# LED_aluminum.net
KiCad netlist of a schematic drawn in Altium Designer
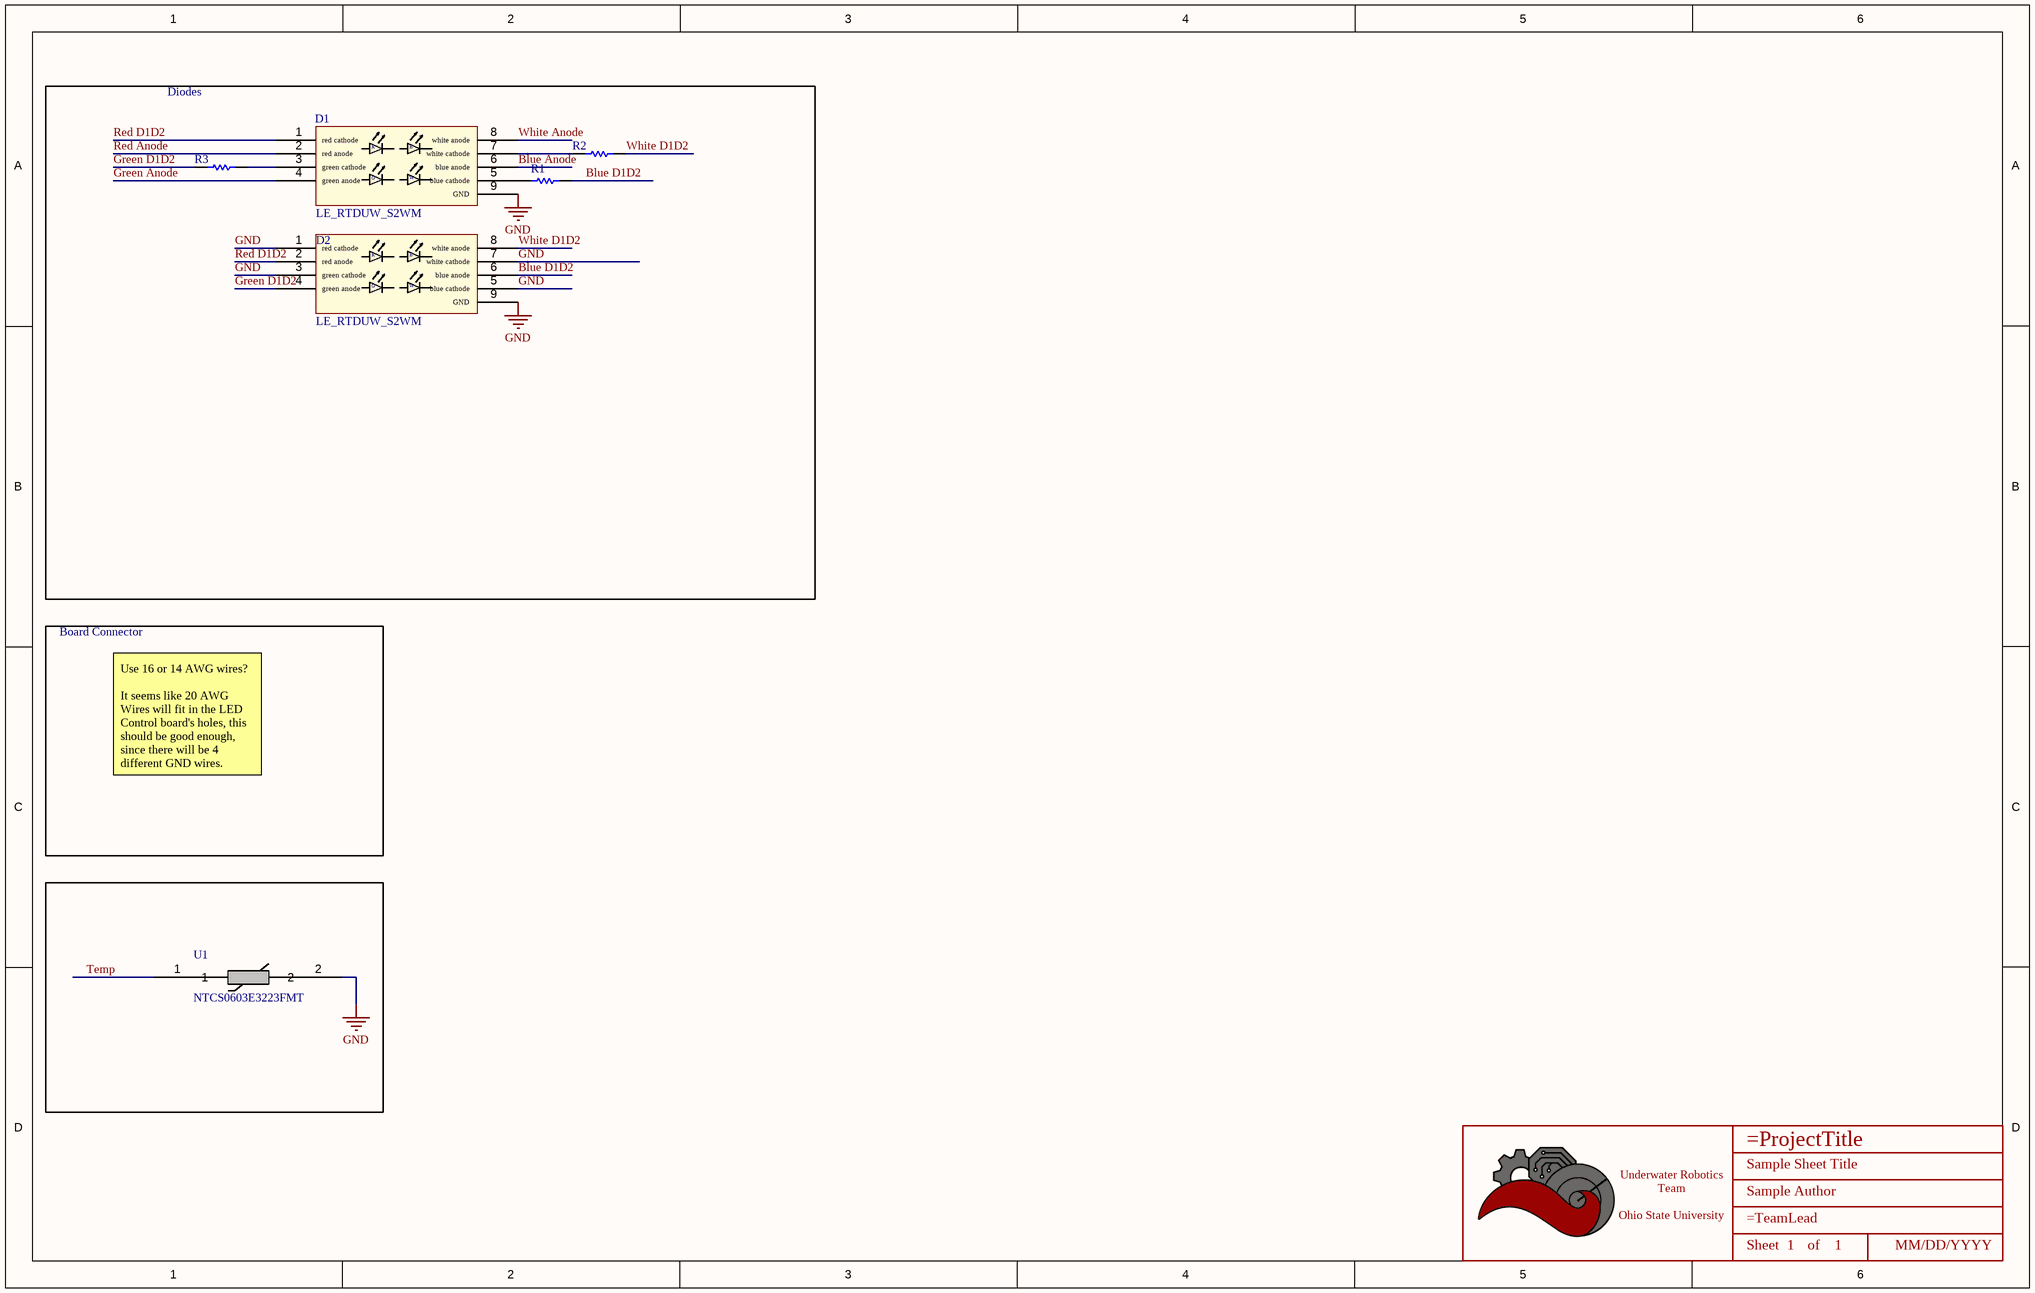
[diagram p0: LED_aluminum.SchDoc]

(export (version "E")
  (design (tool "Eeschema 10.0.6"))
  (components
    (comp (ref "*")
      (value "Title_Block")
      (footprint "LOGO")
      (description "UWRT Schematic Title Block Template\r\n\r\nCreated June 2021, Dylan Trainor")
      (libsource (lib "UWRT") (part "Title_Block"))
    )
    (comp (ref "D1")
      (value "LE_RTDUW_S2WM")
      (footprint "LE_RTDUW_S2WM")
      (description "LED OSTAR RGBW 625/527/453NM SMD")
      (libsource (lib "Diodes") (part "LE_RTDUW_S2WM"))
    )
    (comp (ref "D2")
      (value "LE_RTDUW_S2WM")
      (footprint "LE_RTDUW_S2WM")
      (description "LED OSTAR RGBW 625/527/453NM SMD")
      (libsource (lib "Diodes") (part "LE_RTDUW_S2WM"))
    )
    (comp (ref "R1")
      (value "Jumper 2512(6432)")
      (footprint "RESC2512(6432)_L")
      (description "Jumper 2512 (6432 Metric)")
      (fields (field (name "TOLERANCE") "None"))
      (libsource (lib "") (part "RES_1"))
    )
    (comp (ref "R2")
      (value "ERJ-8GEY0R00V")
      (footprint "RESC3216X70X50NL05T20")
      (fields (field (name "MANUFACTURER") "Panasonic"))
      (libsource (lib "Altium Content Vault") (part "RES"))
    )
    (comp (ref "R3")
      (value "Jumper 2512(6432)")
      (footprint "RESC2512(6432)_L")
      (fields (field (name "MANUFACTURER") "Panasonic") (field (name "PART NUMBER") "ERJ-8GEY0R00V"))
      (libsource (lib "Altium Content Vault") (part "RES"))
    )
    (comp (ref "U1")
      (value "NTCS0603E3223FMT")
      (footprint "NTCS0603_VIS")
      (fields (field (name "TOLERANCE") "1%"))
      (libsource (lib "Altium Content Vault") (part "NTCS0603E3223FMT"))
    )
  )
  (nets
    (net (code "1") (name "/Blue Anode") (class "Default")
      (node (ref "D1") (pin "6") (pinfunction "blue_anode_6") (pintype "passive"))
    )
    (net (code "2") (name "/Blue D1D2") (class "Default")
      (node (ref "D2") (pin "6") (pinfunction "blue_anode_6") (pintype "passive"))
      (node (ref "R1") (pin "2") (pinfunction "2_2") (pintype "passive"))
    )
    (net (code "3") (name "/Green Anode") (class "Default")
      (node (ref "D1") (pin "4") (pinfunction "green_anode_4") (pintype "passive"))
    )
    (net (code "4") (name "/Green D1D2") (class "Default")
      (node (ref "D2") (pin "4") (pinfunction "green_anode_4") (pintype "passive"))
      (node (ref "R3") (pin "2") (pinfunction "2_2") (pintype "passive"))
    )
    (net (code "5") (name "/Red Anode") (class "Default")
      (node (ref "D1") (pin "2") (pinfunction "red_anode_2") (pintype "passive"))
    )
    (net (code "6") (name "/Red D1D2") (class "Default")
      (node (ref "D1") (pin "1") (pinfunction "red_cathode_1") (pintype "passive"))
      (node (ref "D2") (pin "2") (pinfunction "red_anode_2") (pintype "passive"))
    )
    (net (code "7") (name "/Temp") (class "Default")
      (node (ref "U1") (pin "1") (pinfunction "1_1") (pintype "passive"))
    )
    (net (code "8") (name "/White Anode") (class "Default")
      (node (ref "D1") (pin "8") (pinfunction "white_anode_8") (pintype "passive"))
    )
    (net (code "9") (name "/White D1D2") (class "Default")
      (node (ref "D2") (pin "8") (pinfunction "white_anode_8") (pintype "passive"))
      (node (ref "R2") (pin "1") (pinfunction "1_1") (pintype "passive"))
    )
    (net (code "10") (name "GND") (class "Default")
      (node (ref "D1") (pin "9") (pinfunction "GND_9") (pintype "passive"))
      (node (ref "D2") (pin "1") (pinfunction "red_cathode_1") (pintype "passive"))
      (node (ref "D2") (pin "3") (pinfunction "green_cathode_3") (pintype "passive"))
      (node (ref "D2") (pin "5") (pinfunction "blue_cathode_5") (pintype "passive"))
      (node (ref "D2") (pin "7") (pinfunction "white_cathode_7") (pintype "passive"))
      (node (ref "D2") (pin "9") (pinfunction "GND_9") (pintype "passive"))
      (node (ref "U1") (pin "2") (pinfunction "2_2") (pintype "passive"))
    )
    (net (code "11") (name "Net-(D1-blue_cathode)") (class "Default")
      (node (ref "D1") (pin "5") (pinfunction "blue_cathode_5") (pintype "passive"))
      (node (ref "R1") (pin "1") (pinfunction "1_1") (pintype "passive"))
    )
    (net (code "12") (name "Net-(D1-green_cathode)") (class "Default")
      (node (ref "D1") (pin "3") (pinfunction "green_cathode_3") (pintype "passive"))
      (node (ref "R3") (pin "1") (pinfunction "1_1") (pintype "passive"))
    )
    (net (code "13") (name "Net-(D1-white_cathode)") (class "Default")
      (node (ref "D1") (pin "7") (pinfunction "white_cathode_7") (pintype "passive"))
      (node (ref "R2") (pin "2") (pinfunction "2_2") (pintype "passive"))
    )
  )
)
